# Power.net
KiCad netlist of a schematic drawn in Altium Designer
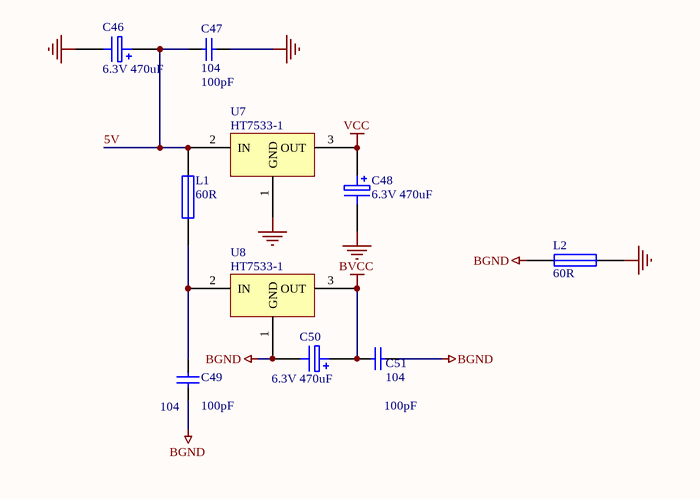
[diagram p0: Power.SchDoc]

(export (version "E")
  (design (tool "Eeschema 10.0.6"))
  (components
    (comp (ref "C46")
      (value "6.3V 470uF")
      (footprint "0603_C")
      (description "Electrolytic Capacitor")
      (libsource (lib "Extra_Board_Mini") (part "ELECTRO1"))
    )
    (comp (ref "C47")
      (value "104")
      (footprint "RAD-0.3")
      (description "Capacitor")
      (fields (field (name "ALTIUM_VALUE") "100pF") (field (name "PUBLISHER") "Altium Limited"))
      (libsource (lib "Extra_Board_Mini") (part "Cap"))
    )
    (comp (ref "C48")
      (value "6.3V 470uF")
      (footprint "0603_C")
      (description "Electrolytic Capacitor")
      (libsource (lib "Extra_Board_Mini") (part "ELECTRO1"))
    )
    (comp (ref "C49")
      (value "104")
      (footprint "RAD-0.3")
      (description "Capacitor")
      (fields (field (name "ALTIUM_VALUE") "100pF") (field (name "PUBLISHER") "Altium Limited"))
      (libsource (lib "Extra_Board_Mini") (part "Cap"))
    )
    (comp (ref "C50")
      (value "6.3V 470uF")
      (footprint "0603_C")
      (description "Electrolytic Capacitor")
      (libsource (lib "Extra_Board_Mini") (part "ELECTRO1"))
    )
    (comp (ref "C51")
      (value "104")
      (footprint "RAD-0.3")
      (description "Capacitor")
      (fields (field (name "ALTIUM_VALUE") "100pF") (field (name "PUBLISHER") "Altium Limited"))
      (libsource (lib "Extra_Board_Mini") (part "Cap"))
    )
    (comp (ref "L1")
      (value "60R")
      (footprint "0603")
      (description "Fuse")
      (libsource (lib "Extra_Board_Mini") (part "FUSE1"))
    )
    (comp (ref "L2")
      (value "60R")
      (footprint "0603")
      (description "Fuse")
      (libsource (lib "Extra_Board_Mini") (part "FUSE1"))
    )
    (comp (ref "U7")
      (value "HT7533-1")
      (footprint "SOT89")
      (libsource (lib "Extra_Board_Mini") (part "HT7533-1"))
    )
    (comp (ref "U8")
      (value "HT7533-1")
      (footprint "SOT89")
      (libsource (lib "Extra_Board_Mini") (part "HT7533-1"))
    )
  )
  (nets
    (net (code "1") (name "/5V") (class "Default")
      (node (ref "C46") (pin "1") (pinfunction "1_1") (pintype "passive"))
      (node (ref "C47") (pin "2") (pinfunction "2_2") (pintype "passive"))
      (node (ref "L1") (pin "1") (pinfunction "1_1") (pintype "passive"))
      (node (ref "U7") (pin "2") (pinfunction "IN_2") (pintype "passive"))
    )
    (net (code "2") (name "BGND") (class "Default")
      (node (ref "C49") (pin "2") (pinfunction "2_2") (pintype "passive"))
      (node (ref "C50") (pin "2") (pinfunction "2_2") (pintype "passive"))
      (node (ref "C51") (pin "1") (pinfunction "1_1") (pintype "passive"))
      (node (ref "L2") (pin "1") (pinfunction "1_1") (pintype "passive"))
      (node (ref "U8") (pin "1") (pinfunction "GND_1") (pintype "passive"))
    )
    (net (code "3") (name "BVCC") (class "Default")
      (node (ref "C50") (pin "1") (pinfunction "1_1") (pintype "passive"))
      (node (ref "C51") (pin "2") (pinfunction "2_2") (pintype "passive"))
      (node (ref "U8") (pin "3") (pinfunction "OUT_3") (pintype "passive"))
    )
    (net (code "4") (name "GND") (class "Default")
      (node (ref "C46") (pin "2") (pinfunction "2_2") (pintype "passive"))
      (node (ref "C47") (pin "1") (pinfunction "1_1") (pintype "passive"))
      (node (ref "C48") (pin "2") (pinfunction "2_2") (pintype "passive"))
      (node (ref "L2") (pin "2") (pinfunction "2_2") (pintype "passive"))
      (node (ref "U7") (pin "1") (pinfunction "GND_1") (pintype "passive"))
    )
    (net (code "5") (name "Net-(U8-IN)") (class "Default")
      (node (ref "C49") (pin "1") (pinfunction "1_1") (pintype "passive"))
      (node (ref "L1") (pin "2") (pinfunction "2_2") (pintype "passive"))
      (node (ref "U8") (pin "2") (pinfunction "IN_2") (pintype "passive"))
    )
    (net (code "6") (name "VCC") (class "Default")
      (node (ref "C48") (pin "1") (pinfunction "1_1") (pintype "passive"))
      (node (ref "U7") (pin "3") (pinfunction "OUT_3") (pintype "passive"))
    )
  )
)
